# Schematic.net
KiCad netlist of a schematic drawn in Altium Designer
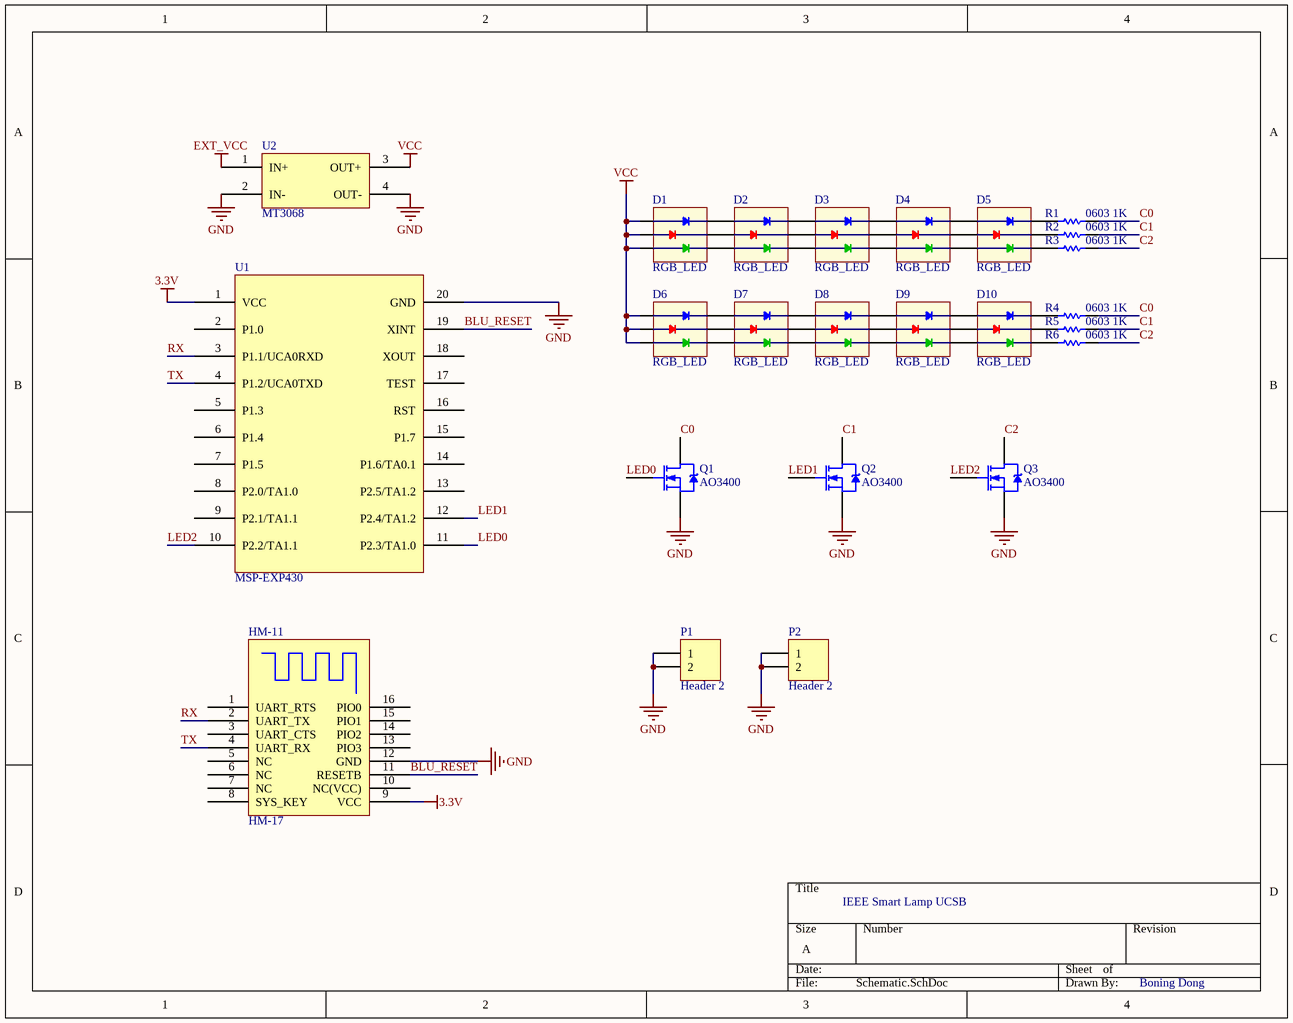
[diagram p0: Schematic.SchDoc]

(export (version "E")
  (design (tool "Eeschema 10.0.6"))
  (components
    (comp (ref "D1")
      (value "RGB_LED")
      (footprint "LED5050")
      (libsource (lib "Miscellaneous Devices") (part "RGB_LED"))
    )
    (comp (ref "D2")
      (value "RGB_LED")
      (footprint "LED5050")
      (libsource (lib "Miscellaneous Devices") (part "RGB_LED"))
    )
    (comp (ref "D3")
      (value "RGB_LED")
      (footprint "LED5050")
      (libsource (lib "Miscellaneous Devices") (part "RGB_LED"))
    )
    (comp (ref "D4")
      (value "RGB_LED")
      (footprint "LED5050")
      (libsource (lib "Miscellaneous Devices") (part "RGB_LED"))
    )
    (comp (ref "D5")
      (value "RGB_LED")
      (footprint "LED5050")
      (libsource (lib "Miscellaneous Devices") (part "RGB_LED"))
    )
    (comp (ref "D6")
      (value "RGB_LED")
      (footprint "LED5050")
      (libsource (lib "Miscellaneous Devices") (part "RGB_LED"))
    )
    (comp (ref "D7")
      (value "RGB_LED")
      (footprint "LED5050")
      (libsource (lib "Miscellaneous Devices") (part "RGB_LED"))
    )
    (comp (ref "D8")
      (value "RGB_LED")
      (footprint "LED5050")
      (libsource (lib "Miscellaneous Devices") (part "RGB_LED"))
    )
    (comp (ref "D9")
      (value "RGB_LED")
      (footprint "LED5050")
      (libsource (lib "Miscellaneous Devices") (part "RGB_LED"))
    )
    (comp (ref "D10")
      (value "RGB_LED")
      (footprint "LED5050")
      (libsource (lib "Miscellaneous Devices") (part "RGB_LED"))
    )
    (comp (ref "HM-11")
      (value "HM-17")
      (footprint "HM_05_06_07_11_13_17")
      (libsource (lib "Modules") (part "HM-17"))
    )
    (comp (ref "P1")
      (value "Header 2")
      (footprint "HDR1X2")
      (description "Header, 2-Pin")
      (fields (field (name "PUBLISHER") "Altium Limited"))
      (libsource (lib "Miscellaneous Connectors") (part "Header 2"))
    )
    (comp (ref "P2")
      (value "Header 2")
      (footprint "HDR1X2")
      (description "Header, 2-Pin")
      (fields (field (name "PUBLISHER") "Altium Limited"))
      (libsource (lib "Miscellaneous Connectors") (part "Header 2"))
    )
    (comp (ref "Q1")
      (value "AO3400")
      (footprint "SOT23")
      (description "N-Channel Power MOSFET")
      (fields (field (name "PUBLISHER") "Altium Limited"))
      (libsource (lib "Transistor") (part "NMOS"))
    )
    (comp (ref "Q2")
      (value "AO3400")
      (footprint "SOT23")
      (description "N-Channel Power MOSFET")
      (fields (field (name "PUBLISHER") "Altium Limited"))
      (libsource (lib "Transistor") (part "NMOS"))
    )
    (comp (ref "Q3")
      (value "AO3400")
      (footprint "SOT23")
      (description "N-Channel Power MOSFET")
      (fields (field (name "PUBLISHER") "Altium Limited"))
      (libsource (lib "Transistor") (part "NMOS"))
    )
    (comp (ref "R1")
      (value "0603")
      (footprint "D0603")
      (description "Resistor")
      (fields (field (name "ALTIUM_VALUE") "1K") (field (name "PUBLISHER") "Altium Limited"))
      (libsource (lib "Miscellaneous Devices") (part "Res1"))
    )
    (comp (ref "R2")
      (value "0603")
      (footprint "D0603")
      (description "Resistor")
      (fields (field (name "ALTIUM_VALUE") "1K") (field (name "PUBLISHER") "Altium Limited"))
      (libsource (lib "Miscellaneous Devices") (part "Res1"))
    )
    (comp (ref "R3")
      (value "0603")
      (footprint "D0603")
      (description "Resistor")
      (fields (field (name "ALTIUM_VALUE") "1K") (field (name "PUBLISHER") "Altium Limited"))
      (libsource (lib "Miscellaneous Devices") (part "Res1"))
    )
    (comp (ref "R4")
      (value "0603")
      (footprint "D0603")
      (description "Resistor")
      (fields (field (name "ALTIUM_VALUE") "1K") (field (name "PUBLISHER") "Altium Limited"))
      (libsource (lib "Miscellaneous Devices") (part "Res1"))
    )
    (comp (ref "R5")
      (value "0603")
      (footprint "D0603")
      (description "Resistor")
      (fields (field (name "ALTIUM_VALUE") "1K") (field (name "PUBLISHER") "Altium Limited"))
      (libsource (lib "Miscellaneous Devices") (part "Res1"))
    )
    (comp (ref "R6")
      (value "0603")
      (footprint "D0603")
      (description "Resistor")
      (fields (field (name "ALTIUM_VALUE") "1K") (field (name "PUBLISHER") "Altium Limited"))
      (libsource (lib "Miscellaneous Devices") (part "Res1"))
    )
    (comp (ref "U1")
      (value "MSP-EXP430")
      (footprint "MSP-EXP430")
      (description "MSP-EXP430 Connectors")
      (libsource (lib "Board Extenders") (part "MSP-EXP430"))
    )
    (comp (ref "U2")
      (value "MT3068")
      (footprint "MT3068-usb")
      (description "MT3068 Boost converter with micro USB")
      (libsource (lib "Modules") (part "MT3068-USB"))
    )
  )
  (nets
    (net (code "1") (name "/BLU_RESET") (class "Default")
      (node (ref "HM-11") (pin "11") (pinfunction "RESETB_11") (pintype "passive"))
      (node (ref "U1") (pin "19") (pinfunction "XINT_19") (pintype "passive"))
    )
    (net (code "2") (name "/C0") (class "Default")
      (node (ref "Q1") (pin "2") (pinfunction "D_2") (pintype "passive"))
      (node (ref "R1") (pin "2") (pinfunction "2_2") (pintype "passive"))
      (node (ref "R4") (pin "2") (pinfunction "2_2") (pintype "passive"))
    )
    (net (code "3") (name "/C1") (class "Default")
      (node (ref "Q2") (pin "2") (pinfunction "D_2") (pintype "passive"))
      (node (ref "R2") (pin "2") (pinfunction "2_2") (pintype "passive"))
      (node (ref "R5") (pin "2") (pinfunction "2_2") (pintype "passive"))
    )
    (net (code "4") (name "/C2") (class "Default")
      (node (ref "Q3") (pin "2") (pinfunction "D_2") (pintype "passive"))
      (node (ref "R3") (pin "2") (pinfunction "2_2") (pintype "passive"))
      (node (ref "R6") (pin "2") (pinfunction "2_2") (pintype "passive"))
    )
    (net (code "5") (name "/LED0") (class "Default")
      (node (ref "Q1") (pin "1") (pinfunction "G_1") (pintype "passive"))
      (node (ref "U1") (pin "11") (pinfunction "P2.3/TA1.0_11") (pintype "passive"))
    )
    (net (code "6") (name "/LED1") (class "Default")
      (node (ref "Q2") (pin "1") (pinfunction "G_1") (pintype "passive"))
      (node (ref "U1") (pin "12") (pinfunction "P2.4/TA1.2_12") (pintype "passive"))
    )
    (net (code "7") (name "/LED2") (class "Default")
      (node (ref "Q3") (pin "1") (pinfunction "G_1") (pintype "passive"))
      (node (ref "U1") (pin "10") (pinfunction "P2.2/TA1.1_10") (pintype "passive"))
    )
    (net (code "8") (name "/RX") (class "Default")
      (node (ref "HM-11") (pin "2") (pinfunction "UART_TX_2") (pintype "passive"))
      (node (ref "U1") (pin "3") (pinfunction "P1.1/UCA0RXD_3") (pintype "passive"))
    )
    (net (code "9") (name "/TX") (class "Default")
      (node (ref "HM-11") (pin "4") (pinfunction "UART_RX_4") (pintype "passive"))
      (node (ref "U1") (pin "4") (pinfunction "P1.2/UCA0TXD_4") (pintype "passive"))
    )
    (net (code "10") (name "3.3V") (class "Default")
      (node (ref "HM-11") (pin "9") (pinfunction "VCC_9") (pintype "passive"))
      (node (ref "U1") (pin "1") (pinfunction "VCC_1") (pintype "passive"))
    )
    (net (code "11") (name "EXT_VCC") (class "Default")
      (node (ref "U2") (pin "1") (pinfunction "IN+_1") (pintype "passive"))
    )
    (net (code "12") (name "GND") (class "Default")
      (node (ref "HM-11") (pin "12") (pinfunction "GND_12") (pintype "passive"))
      (node (ref "P1") (pin "1") (pinfunction "1_1") (pintype "passive"))
      (node (ref "P1") (pin "2") (pinfunction "2_2") (pintype "passive"))
      (node (ref "P2") (pin "1") (pinfunction "1_1") (pintype "passive"))
      (node (ref "P2") (pin "2") (pinfunction "2_2") (pintype "passive"))
      (node (ref "Q1") (pin "3") (pinfunction "S_3") (pintype "passive"))
      (node (ref "Q2") (pin "3") (pinfunction "S_3") (pintype "passive"))
      (node (ref "Q3") (pin "3") (pinfunction "S_3") (pintype "passive"))
      (node (ref "U1") (pin "20") (pinfunction "GND_20") (pintype "passive"))
      (node (ref "U2") (pin "2") (pinfunction "IN-_2") (pintype "passive"))
      (node (ref "U2") (pin "4") (pinfunction "OUT-_4") (pintype "passive"))
    )
    (net (code "13") (name "Net-(D1-B-)") (class "Default")
      (node (ref "D1") (pin "4") (pinfunction "B-_4") (pintype "passive"))
      (node (ref "D2") (pin "3") (pinfunction "B+_3") (pintype "passive"))
    )
    (net (code "14") (name "Net-(D1-G-)") (class "Default")
      (node (ref "D1") (pin "5") (pinfunction "G-_5") (pintype "passive"))
      (node (ref "D2") (pin "2") (pinfunction "G+_2") (pintype "passive"))
    )
    (net (code "15") (name "Net-(D1-R-)") (class "Default")
      (node (ref "D1") (pin "6") (pinfunction "R-_6") (pintype "passive"))
      (node (ref "D2") (pin "1") (pinfunction "R+_1") (pintype "passive"))
    )
    (net (code "16") (name "Net-(D2-B-)") (class "Default")
      (node (ref "D2") (pin "4") (pinfunction "B-_4") (pintype "passive"))
      (node (ref "D3") (pin "3") (pinfunction "B+_3") (pintype "passive"))
    )
    (net (code "17") (name "Net-(D2-G-)") (class "Default")
      (node (ref "D2") (pin "5") (pinfunction "G-_5") (pintype "passive"))
      (node (ref "D3") (pin "2") (pinfunction "G+_2") (pintype "passive"))
    )
    (net (code "18") (name "Net-(D2-R-)") (class "Default")
      (node (ref "D2") (pin "6") (pinfunction "R-_6") (pintype "passive"))
      (node (ref "D3") (pin "1") (pinfunction "R+_1") (pintype "passive"))
    )
    (net (code "19") (name "Net-(D3-B-)") (class "Default")
      (node (ref "D3") (pin "4") (pinfunction "B-_4") (pintype "passive"))
      (node (ref "D4") (pin "3") (pinfunction "B+_3") (pintype "passive"))
    )
    (net (code "20") (name "Net-(D3-G-)") (class "Default")
      (node (ref "D3") (pin "5") (pinfunction "G-_5") (pintype "passive"))
      (node (ref "D4") (pin "2") (pinfunction "G+_2") (pintype "passive"))
    )
    (net (code "21") (name "Net-(D3-R-)") (class "Default")
      (node (ref "D3") (pin "6") (pinfunction "R-_6") (pintype "passive"))
      (node (ref "D4") (pin "1") (pinfunction "R+_1") (pintype "passive"))
    )
    (net (code "22") (name "Net-(D4-B-)") (class "Default")
      (node (ref "D4") (pin "4") (pinfunction "B-_4") (pintype "passive"))
      (node (ref "D5") (pin "3") (pinfunction "B+_3") (pintype "passive"))
    )
    (net (code "23") (name "Net-(D4-G-)") (class "Default")
      (node (ref "D4") (pin "5") (pinfunction "G-_5") (pintype "passive"))
      (node (ref "D5") (pin "2") (pinfunction "G+_2") (pintype "passive"))
    )
    (net (code "24") (name "Net-(D4-R-)") (class "Default")
      (node (ref "D4") (pin "6") (pinfunction "R-_6") (pintype "passive"))
      (node (ref "D5") (pin "1") (pinfunction "R+_1") (pintype "passive"))
    )
    (net (code "25") (name "Net-(D5-B-)") (class "Default")
      (node (ref "D5") (pin "4") (pinfunction "B-_4") (pintype "passive"))
      (node (ref "R3") (pin "1") (pinfunction "1_1") (pintype "passive"))
    )
    (net (code "26") (name "Net-(D5-G-)") (class "Default")
      (node (ref "D5") (pin "5") (pinfunction "G-_5") (pintype "passive"))
      (node (ref "R2") (pin "1") (pinfunction "1_1") (pintype "passive"))
    )
    (net (code "27") (name "Net-(D5-R-)") (class "Default")
      (node (ref "D5") (pin "6") (pinfunction "R-_6") (pintype "passive"))
      (node (ref "R1") (pin "1") (pinfunction "1_1") (pintype "passive"))
    )
    (net (code "28") (name "Net-(D6-B-)") (class "Default")
      (node (ref "D6") (pin "4") (pinfunction "B-_4") (pintype "passive"))
      (node (ref "D7") (pin "3") (pinfunction "B+_3") (pintype "passive"))
    )
    (net (code "29") (name "Net-(D6-G-)") (class "Default")
      (node (ref "D6") (pin "5") (pinfunction "G-_5") (pintype "passive"))
      (node (ref "D7") (pin "2") (pinfunction "G+_2") (pintype "passive"))
    )
    (net (code "30") (name "Net-(D6-R-)") (class "Default")
      (node (ref "D6") (pin "6") (pinfunction "R-_6") (pintype "passive"))
      (node (ref "D7") (pin "1") (pinfunction "R+_1") (pintype "passive"))
    )
    (net (code "31") (name "Net-(D7-B-)") (class "Default")
      (node (ref "D7") (pin "4") (pinfunction "B-_4") (pintype "passive"))
      (node (ref "D8") (pin "3") (pinfunction "B+_3") (pintype "passive"))
    )
    (net (code "32") (name "Net-(D7-G-)") (class "Default")
      (node (ref "D7") (pin "5") (pinfunction "G-_5") (pintype "passive"))
      (node (ref "D8") (pin "2") (pinfunction "G+_2") (pintype "passive"))
    )
    (net (code "33") (name "Net-(D7-R-)") (class "Default")
      (node (ref "D7") (pin "6") (pinfunction "R-_6") (pintype "passive"))
      (node (ref "D8") (pin "1") (pinfunction "R+_1") (pintype "passive"))
    )
    (net (code "34") (name "Net-(D8-B-)") (class "Default")
      (node (ref "D8") (pin "4") (pinfunction "B-_4") (pintype "passive"))
      (node (ref "D9") (pin "3") (pinfunction "B+_3") (pintype "passive"))
    )
    (net (code "35") (name "Net-(D8-G-)") (class "Default")
      (node (ref "D8") (pin "5") (pinfunction "G-_5") (pintype "passive"))
      (node (ref "D9") (pin "2") (pinfunction "G+_2") (pintype "passive"))
    )
    (net (code "36") (name "Net-(D8-R-)") (class "Default")
      (node (ref "D8") (pin "6") (pinfunction "R-_6") (pintype "passive"))
      (node (ref "D9") (pin "1") (pinfunction "R+_1") (pintype "passive"))
    )
    (net (code "37") (name "Net-(D10-B+)") (class "Default")
      (node (ref "D10") (pin "3") (pinfunction "B+_3") (pintype "passive"))
      (node (ref "D9") (pin "4") (pinfunction "B-_4") (pintype "passive"))
    )
    (net (code "38") (name "Net-(D10-B-)") (class "Default")
      (node (ref "D10") (pin "4") (pinfunction "B-_4") (pintype "passive"))
      (node (ref "R6") (pin "1") (pinfunction "1_1") (pintype "passive"))
    )
    (net (code "39") (name "Net-(D10-G+)") (class "Default")
      (node (ref "D10") (pin "2") (pinfunction "G+_2") (pintype "passive"))
      (node (ref "D9") (pin "5") (pinfunction "G-_5") (pintype "passive"))
    )
    (net (code "40") (name "Net-(D10-G-)") (class "Default")
      (node (ref "D10") (pin "5") (pinfunction "G-_5") (pintype "passive"))
      (node (ref "R5") (pin "1") (pinfunction "1_1") (pintype "passive"))
    )
    (net (code "41") (name "Net-(D10-R+)") (class "Default")
      (node (ref "D10") (pin "1") (pinfunction "R+_1") (pintype "passive"))
      (node (ref "D9") (pin "6") (pinfunction "R-_6") (pintype "passive"))
    )
    (net (code "42") (name "Net-(D10-R-)") (class "Default")
      (node (ref "D10") (pin "6") (pinfunction "R-_6") (pintype "passive"))
      (node (ref "R4") (pin "1") (pinfunction "1_1") (pintype "passive"))
    )
    (net (code "43") (name "VCC") (class "Default")
      (node (ref "D1") (pin "1") (pinfunction "R+_1") (pintype "passive"))
      (node (ref "D1") (pin "2") (pinfunction "G+_2") (pintype "passive"))
      (node (ref "D1") (pin "3") (pinfunction "B+_3") (pintype "passive"))
      (node (ref "D6") (pin "1") (pinfunction "R+_1") (pintype "passive"))
      (node (ref "D6") (pin "2") (pinfunction "G+_2") (pintype "passive"))
      (node (ref "D6") (pin "3") (pinfunction "B+_3") (pintype "passive"))
      (node (ref "U2") (pin "3") (pinfunction "OUT+_3") (pintype "passive"))
    )
    (net (code "44") (name "unconnected-(HM-11-NC(VCC)-Pad10)") (class "Default")
      (node (ref "HM-11") (pin "10") (pinfunction "NC(VCC)_10") (pintype "passive"))
    )
    (net (code "45") (name "unconnected-(HM-11-NC-Pad5)") (class "Default")
      (node (ref "HM-11") (pin "5") (pinfunction "NC_5") (pintype "passive"))
    )
    (net (code "46") (name "unconnected-(HM-11-NC-Pad6)") (class "Default")
      (node (ref "HM-11") (pin "6") (pinfunction "NC_6") (pintype "passive"))
    )
    (net (code "47") (name "unconnected-(HM-11-NC-Pad7)") (class "Default")
      (node (ref "HM-11") (pin "7") (pinfunction "NC_7") (pintype "passive"))
    )
    (net (code "48") (name "unconnected-(HM-11-PIO0-Pad16)") (class "Default")
      (node (ref "HM-11") (pin "16") (pinfunction "PIO0_16") (pintype "passive"))
    )
    (net (code "49") (name "unconnected-(HM-11-PIO1-Pad15)") (class "Default")
      (node (ref "HM-11") (pin "15") (pinfunction "PIO1_15") (pintype "passive"))
    )
    (net (code "50") (name "unconnected-(HM-11-PIO2-Pad14)") (class "Default")
      (node (ref "HM-11") (pin "14") (pinfunction "PIO2_14") (pintype "passive"))
    )
    (net (code "51") (name "unconnected-(HM-11-PIO3-Pad13)") (class "Default")
      (node (ref "HM-11") (pin "13") (pinfunction "PIO3_13") (pintype "passive"))
    )
    (net (code "52") (name "unconnected-(HM-11-SYS_KEY-Pad8)") (class "Default")
      (node (ref "HM-11") (pin "8") (pinfunction "SYS_KEY_8") (pintype "passive"))
    )
    (net (code "53") (name "unconnected-(HM-11-UART_CTS-Pad3)") (class "Default")
      (node (ref "HM-11") (pin "3") (pinfunction "UART_CTS_3") (pintype "passive"))
    )
    (net (code "54") (name "unconnected-(HM-11-UART_RTS-Pad1)") (class "Default")
      (node (ref "HM-11") (pin "1") (pinfunction "UART_RTS_1") (pintype "passive"))
    )
    (net (code "55") (name "unconnected-(U1-P1.0-Pad2)") (class "Default")
      (node (ref "U1") (pin "2") (pinfunction "P1.0_2") (pintype "passive"))
    )
    (net (code "56") (name "unconnected-(U1-P1.3-Pad5)") (class "Default")
      (node (ref "U1") (pin "5") (pinfunction "P1.3_5") (pintype "passive"))
    )
    (net (code "57") (name "unconnected-(U1-P1.4-Pad6)") (class "Default")
      (node (ref "U1") (pin "6") (pinfunction "P1.4_6") (pintype "passive"))
    )
    (net (code "58") (name "unconnected-(U1-P1.5-Pad7)") (class "Default")
      (node (ref "U1") (pin "7") (pinfunction "P1.5_7") (pintype "passive"))
    )
    (net (code "59") (name "unconnected-(U1-P1.6{slash}TA0.1-Pad14)") (class "Default")
      (node (ref "U1") (pin "14") (pinfunction "P1.6/TA0.1_14") (pintype "passive"))
    )
    (net (code "60") (name "unconnected-(U1-P1.7-Pad15)") (class "Default")
      (node (ref "U1") (pin "15") (pinfunction "P1.7_15") (pintype "passive"))
    )
    (net (code "61") (name "unconnected-(U1-P2.0{slash}TA1.0-Pad8)") (class "Default")
      (node (ref "U1") (pin "8") (pinfunction "P2.0/TA1.0_8") (pintype "passive"))
    )
    (net (code "62") (name "unconnected-(U1-P2.1{slash}TA1.1-Pad9)") (class "Default")
      (node (ref "U1") (pin "9") (pinfunction "P2.1/TA1.1_9") (pintype "passive"))
    )
    (net (code "63") (name "unconnected-(U1-P2.5{slash}TA1.2-Pad13)") (class "Default")
      (node (ref "U1") (pin "13") (pinfunction "P2.5/TA1.2_13") (pintype "passive"))
    )
    (net (code "64") (name "unconnected-(U1-RST-Pad16)") (class "Default")
      (node (ref "U1") (pin "16") (pinfunction "RST_16") (pintype "passive"))
    )
    (net (code "65") (name "unconnected-(U1-TEST-Pad17)") (class "Default")
      (node (ref "U1") (pin "17") (pinfunction "TEST_17") (pintype "passive"))
    )
    (net (code "66") (name "unconnected-(U1-XOUT-Pad18)") (class "Default")
      (node (ref "U1") (pin "18") (pinfunction "XOUT_18") (pintype "passive"))
    )
  )
)
